# board.net
KiCad netlist of a schematic drawn in EAGLE
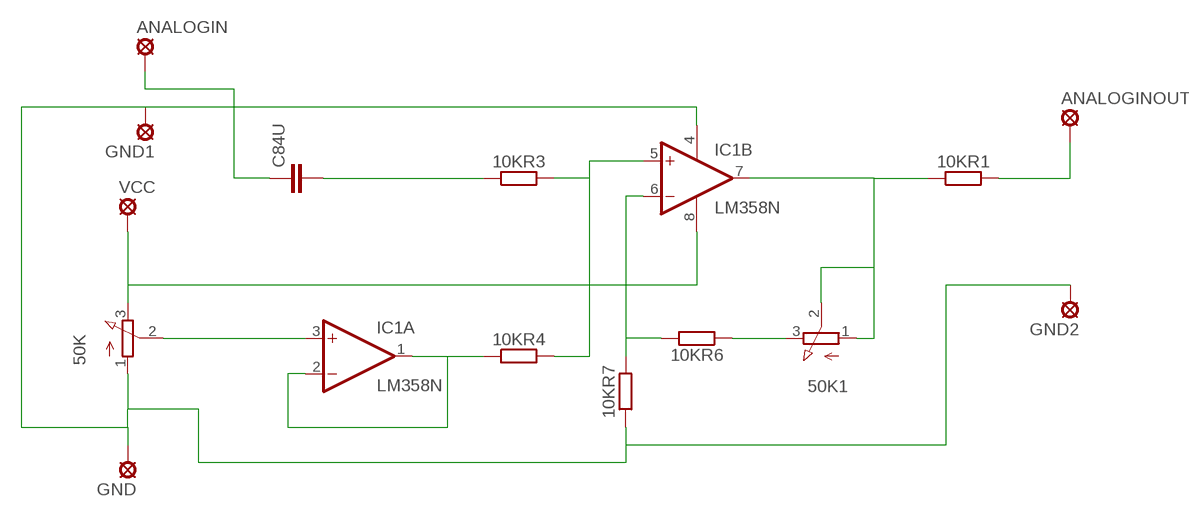
[diagram p0: schematic, sheet 1]

(export (version "E")
  (design (tool "Eeschema 10.0.6"))
  (components
    (comp (ref "10KR1")
      (value "R-EU_0411/12")
      (footprint "eagle-import:0411_12")
      (libsource (lib "eagle-import") (part "R-EU_0411/12"))
    )
    (comp (ref "10KR3")
      (value "R-EU_0411/12")
      (footprint "eagle-import:0411_12")
      (libsource (lib "eagle-import") (part "R-EU_0411/12"))
    )
    (comp (ref "10KR4")
      (value "R-EU_0411/12")
      (footprint "eagle-import:0411_12")
      (libsource (lib "eagle-import") (part "R-EU_0411/12"))
    )
    (comp (ref "10KR6")
      (value "R-EU_0411/12")
      (footprint "eagle-import:0411_12")
      (libsource (lib "eagle-import") (part "R-EU_0411/12"))
    )
    (comp (ref "10KR7")
      (value "R-EU_0411/12")
      (footprint "eagle-import:0411_12")
      (libsource (lib "eagle-import") (part "R-EU_0411/12"))
    )
    (comp (ref "50K")
      (value "3RP/1610N")
      (footprint "eagle-import:3RP_1610N")
      (libsource (lib "eagle-import") (part "3RP/1610N"))
    )
    (comp (ref "50K1")
      (value "3RP/1610N")
      (footprint "eagle-import:3RP_1610N")
      (libsource (lib "eagle-import") (part "3RP/1610N"))
    )
    (comp (ref "ANALOGIN")
      (value "SE11")
      (footprint "eagle-import:SE11")
      (libsource (lib "eagle-import") (part "SE11"))
    )
    (comp (ref "ANALOGINOUT")
      (value "SE11")
      (footprint "eagle-import:SE11")
      (libsource (lib "eagle-import") (part "SE11"))
    )
    (comp (ref "C84U")
      (value "C2.5/6")
      (footprint "eagle-import:C2.5-6")
      (libsource (lib "eagle-import") (part "C2.5/6"))
    )
    (comp (ref "GND")
      (value "SE11")
      (footprint "eagle-import:SE11")
      (libsource (lib "eagle-import") (part "SE11"))
    )
    (comp (ref "GND1")
      (value "SE11")
      (footprint "eagle-import:SE11")
      (libsource (lib "eagle-import") (part "SE11"))
    )
    (comp (ref "GND2")
      (value "SE11")
      (footprint "eagle-import:SE11")
      (libsource (lib "eagle-import") (part "SE11"))
    )
    (comp (ref "IC1")
      (value "LM358N")
      (footprint "eagle-import:DIL08")
      (libsource (lib "eagle-import") (part "LM358N"))
    )
    (comp (ref "VCC")
      (value "SE11")
      (footprint "eagle-import:SE11")
      (libsource (lib "eagle-import") (part "SE11"))
    )
  )
  (nets
    (net (code "1") (name "Net-(10KR1-Pad2)") (class "Default")
      (node (ref "10KR1") (pin "2") (pinfunction "2_2") (pintype "passive"))
      (node (ref "ANALOGINOUT") (pin "MP") (pinfunction "MP_MP") (pintype "passive"))
    )
    (net (code "2") (name "Net-(10KR3-Pad1)") (class "Default")
      (node (ref "10KR3") (pin "1") (pinfunction "1_1") (pintype "passive"))
      (node (ref "C84U") (pin "2") (pinfunction "2_2") (pintype "passive"))
    )
    (net (code "3") (name "Net-(50K-A)") (class "Default")
      (node (ref "10KR7") (pin "1") (pinfunction "1_1") (pintype "passive"))
      (node (ref "50K") (pin "1") (pinfunction "A_1") (pintype "passive"))
      (node (ref "GND") (pin "MP") (pinfunction "MP_MP") (pintype "passive"))
      (node (ref "GND1") (pin "MP") (pinfunction "MP_MP") (pintype "passive"))
      (node (ref "GND2") (pin "MP") (pinfunction "MP_MP") (pintype "passive"))
      (node (ref "IC1") (pin "4") (pinfunction "V-_4") (pintype "power_in"))
    )
    (net (code "4") (name "Net-(50K-E)") (class "Default")
      (node (ref "50K") (pin "3") (pinfunction "E_3") (pintype "passive"))
      (node (ref "IC1") (pin "8") (pinfunction "V+_8") (pintype "power_in"))
      (node (ref "VCC") (pin "MP") (pinfunction "MP_MP") (pintype "passive"))
    )
    (net (code "5") (name "Net-(50K-S)") (class "Default")
      (node (ref "50K") (pin "2") (pinfunction "S_2") (pintype "passive"))
      (node (ref "IC1") (pin "3") (pinfunction "+IN_3") (pintype "input"))
    )
    (net (code "6") (name "Net-(50K1-A)") (class "Default")
      (node (ref "10KR1") (pin "1") (pinfunction "1_1") (pintype "passive"))
      (node (ref "50K1") (pin "1") (pinfunction "A_1") (pintype "passive"))
      (node (ref "50K1") (pin "2") (pinfunction "S_2") (pintype "passive"))
      (node (ref "IC1") (pin "7") (pinfunction "OUT_7") (pintype "output"))
    )
    (net (code "7") (name "Net-(50K1-E)") (class "Default")
      (node (ref "10KR6") (pin "1") (pinfunction "1_1") (pintype "passive"))
      (node (ref "50K1") (pin "3") (pinfunction "E_3") (pintype "passive"))
    )
    (net (code "8") (name "Net-(ANALOGIN-PadMP)") (class "Default")
      (node (ref "ANALOGIN") (pin "MP") (pinfunction "MP_MP") (pintype "passive"))
      (node (ref "C84U") (pin "1") (pinfunction "1_1") (pintype "passive"))
    )
    (net (code "9") (name "Net-(IC1A--IN)") (class "Default")
      (node (ref "10KR4") (pin "1") (pinfunction "1_1") (pintype "passive"))
      (node (ref "IC1") (pin "1") (pinfunction "OUT_1") (pintype "output"))
      (node (ref "IC1") (pin "2") (pinfunction "-IN_2") (pintype "input"))
    )
    (net (code "10") (name "Net-(IC1B-+IN)") (class "Default")
      (node (ref "10KR3") (pin "2") (pinfunction "2_2") (pintype "passive"))
      (node (ref "10KR4") (pin "2") (pinfunction "2_2") (pintype "passive"))
      (node (ref "IC1") (pin "5") (pinfunction "+IN_5") (pintype "input"))
    )
    (net (code "11") (name "Net-(IC1B--IN)") (class "Default")
      (node (ref "10KR6") (pin "2") (pinfunction "2_2") (pintype "passive"))
      (node (ref "10KR7") (pin "2") (pinfunction "2_2") (pintype "passive"))
      (node (ref "IC1") (pin "6") (pinfunction "-IN_6") (pintype "input"))
    )
  )
)
